# CC2650MCURadio.net
KiCad netlist of a schematic drawn in Altium Designer
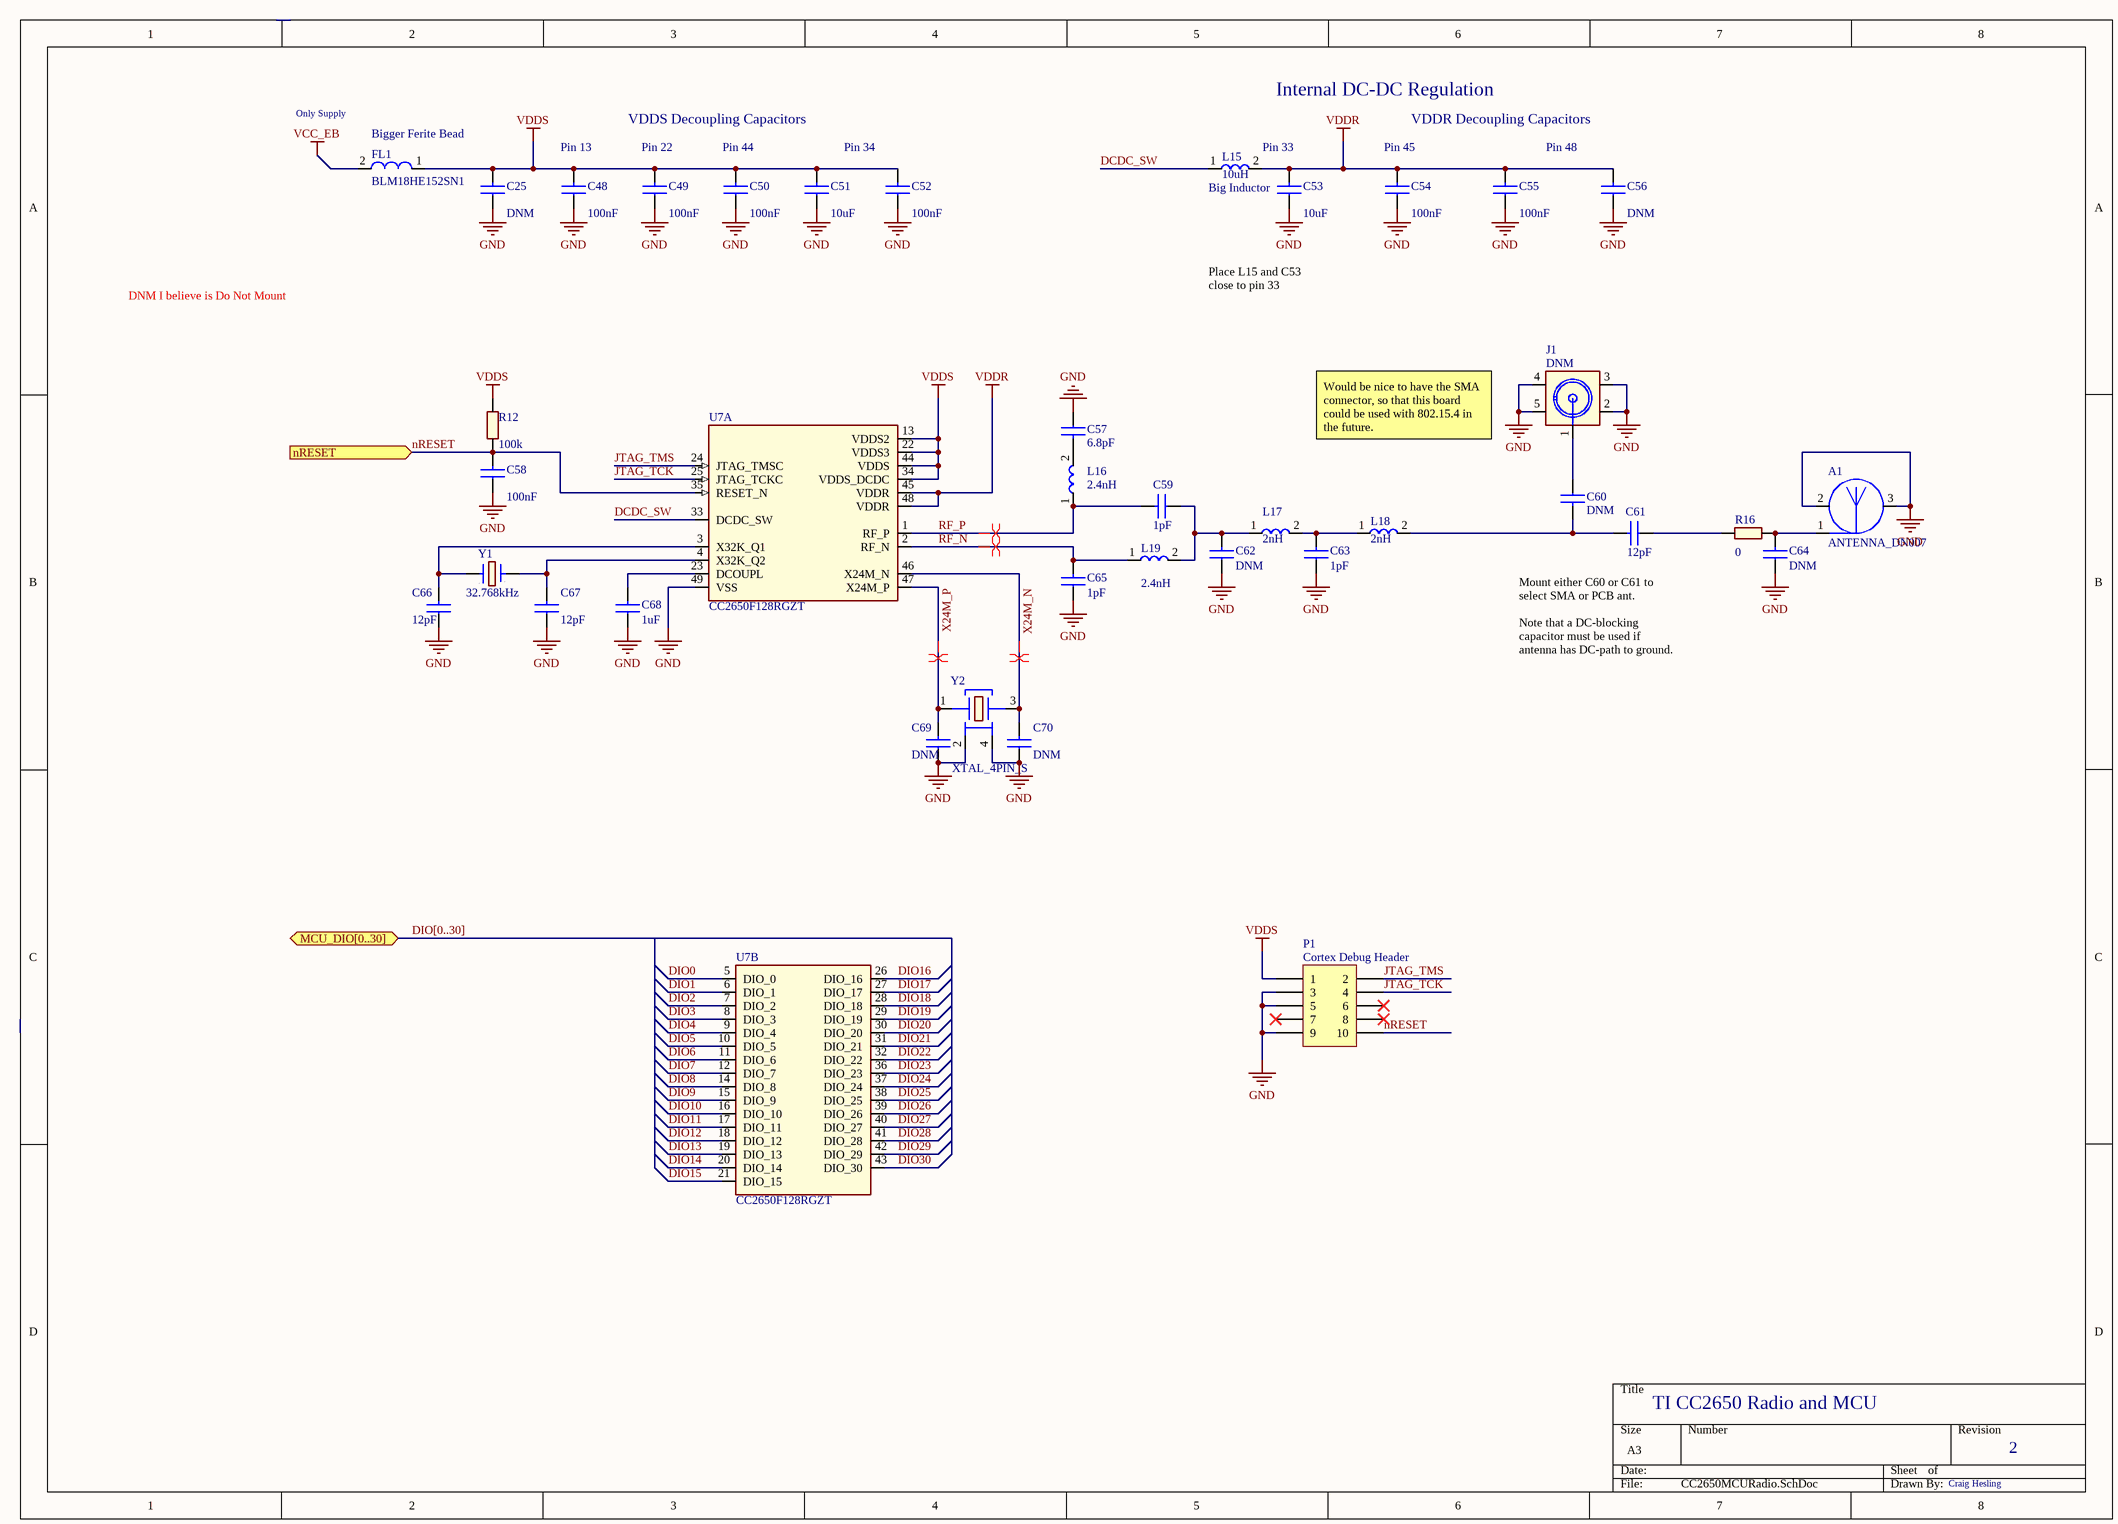
[diagram p0: CC2650MCURadio.SchDoc]

(export (version "E")
  (design (tool "Eeschema 10.0.6"))
  (components
    (comp (ref "A1")
      (value "ANTENNA_DN007")
      (footprint "ANTENNA_DN007AN_NO_MASK")
      (fields (field (name "DESIGNED BY") "Artur Bielinski"))
      (libsource (lib "CC26XX_7X7_DIFF_Library") (part "ANTENNA_DN007"))
    )
    (comp (ref "C25")
      (value "DNM")
      (footprint "CAPC0402(1005)60_N")
      (fields (field (name "VOLTAGE") "CMAX") (field (name "Comment") "CAPACITOR"))
      (libsource (lib "CC26XX_7X7_DIFF_Library") (part "CAPACITOR"))
    )
    (comp (ref "C48")
      (value "100nF")
      (footprint "CAPC0402(1005)60_N")
      (fields (field (name "VOLTAGE") "CMAX") (field (name "Comment") "CAPACITOR"))
      (libsource (lib "CC26XX_7X7_DIFF_Library") (part "CAPACITOR"))
    )
    (comp (ref "C49")
      (value "100nF")
      (footprint "CAPC0402(1005)60_N")
      (fields (field (name "VOLTAGE") "CMAX") (field (name "Comment") "CAPACITOR"))
      (libsource (lib "CC26XX_7X7_DIFF_Library") (part "CAPACITOR"))
    )
    (comp (ref "C50")
      (value "100nF")
      (footprint "CAPC0402(1005)60_N")
      (fields (field (name "VOLTAGE") "CMAX") (field (name "Comment") "CAPACITOR"))
      (libsource (lib "CC26XX_7X7_DIFF_Library") (part "CAPACITOR"))
    )
    (comp (ref "C51")
      (value "10uF")
      (footprint "CAPC0603(1608)100_N")
      (fields (field (name "VOLTAGE") "CMAX") (field (name "Comment") "CAPACITOR"))
      (libsource (lib "CC26XX_7X7_DIFF_Library") (part "CAPACITOR"))
    )
    (comp (ref "C52")
      (value "100nF")
      (footprint "CAPC0603(1608)100_N")
      (fields (field (name "VOLTAGE") "CMAX") (field (name "Comment") "CAPACITOR"))
      (libsource (lib "CC26XX_7X7_DIFF_Library") (part "CAPACITOR"))
    )
    (comp (ref "C53")
      (value "10uF")
      (footprint "CAPC0603(1608)100_N")
      (fields (field (name "VOLTAGE") "CMAX") (field (name "Comment") "CAPACITOR"))
      (libsource (lib "CC26XX_7X7_DIFF_Library") (part "CAPACITOR"))
    )
    (comp (ref "C54")
      (value "100nF")
      (footprint "CAPC0402(1005)60_N")
      (fields (field (name "VOLTAGE") "CMAX") (field (name "Comment") "CAPACITOR"))
      (libsource (lib "CC26XX_7X7_DIFF_Library") (part "CAPACITOR"))
    )
    (comp (ref "C55")
      (value "100nF")
      (footprint "CAPC0402(1005)60_N")
      (fields (field (name "VOLTAGE") "CMAX") (field (name "Comment") "CAPACITOR"))
      (libsource (lib "CC26XX_7X7_DIFF_Library") (part "CAPACITOR"))
    )
    (comp (ref "C56")
      (value "DNM")
      (footprint "CAPC0402(1005)60_N")
      (fields (field (name "VOLTAGE") "CMAX") (field (name "Comment") "CAPACITOR"))
      (libsource (lib "CC26XX_7X7_DIFF_Library") (part "CAPACITOR"))
    )
    (comp (ref "C57")
      (value "6.8pF")
      (footprint "CAPC0402(1005)60_N")
      (fields (field (name "VOLTAGE") "CMAX") (field (name "Comment") "CAPACITOR"))
      (libsource (lib "CC26XX_7X7_DIFF_Library") (part "CAPACITOR"))
    )
    (comp (ref "C58")
      (value "100nF")
      (footprint "CAPC0402(1005)60_N")
      (fields (field (name "VOLTAGE") "CMAX") (field (name "Comment") "CAPACITOR"))
      (libsource (lib "CC26XX_7X7_DIFF_Library") (part "CAPACITOR"))
    )
    (comp (ref "C59")
      (value "1pF")
      (footprint "CAPC0402(1005)60_N")
      (fields (field (name "VOLTAGE") "CMAX") (field (name "Comment") "CAPACITOR"))
      (libsource (lib "CC26XX_7X7_DIFF_Library") (part "CAPACITOR"))
    )
    (comp (ref "C60")
      (value "DNM")
      (footprint "CAPC0402(1005)60_N")
      (fields (field (name "VOLTAGE") "CMAX") (field (name "Comment") "CAPACITOR"))
      (libsource (lib "CC26XX_7X7_DIFF_Library") (part "CAPACITOR"))
    )
    (comp (ref "C61")
      (value "12pF")
      (footprint "CAPC0402(1005)60_N")
      (fields (field (name "VOLTAGE") "CMAX") (field (name "Comment") "CAPACITOR"))
      (libsource (lib "CC26XX_7X7_DIFF_Library") (part "CAPACITOR"))
    )
    (comp (ref "C62")
      (value "DNM")
      (footprint "CAPC0402(1005)60_N")
      (fields (field (name "VOLTAGE") "CMAX") (field (name "Comment") "CAPACITOR"))
      (libsource (lib "CC26XX_7X7_DIFF_Library") (part "CAPACITOR"))
    )
    (comp (ref "C63")
      (value "1pF")
      (footprint "CAPC0402(1005)60_N")
      (fields (field (name "VOLTAGE") "CMAX") (field (name "Comment") "CAPACITOR"))
      (libsource (lib "CC26XX_7X7_DIFF_Library") (part "CAPACITOR"))
    )
    (comp (ref "C64")
      (value "DNM")
      (footprint "CAPC0402(1005)60_N")
      (fields (field (name "VOLTAGE") "CMAX") (field (name "Comment") "CAPACITOR"))
      (libsource (lib "CC26XX_7X7_DIFF_Library") (part "CAPACITOR"))
    )
    (comp (ref "C65")
      (value "1pF")
      (footprint "CAPC0402(1005)60_N")
      (fields (field (name "VOLTAGE") "CMAX") (field (name "Comment") "CAPACITOR"))
      (libsource (lib "CC26XX_7X7_DIFF_Library") (part "CAPACITOR"))
    )
    (comp (ref "C66")
      (value "12pF")
      (footprint "CAPC0402(1005)60_N")
      (fields (field (name "VOLTAGE") "CMAX") (field (name "Comment") "CAPACITOR"))
      (libsource (lib "CC26XX_7X7_DIFF_Library") (part "CAPACITOR"))
    )
    (comp (ref "C67")
      (value "12pF")
      (footprint "CAPC0402(1005)60_N")
      (fields (field (name "VOLTAGE") "CMAX") (field (name "Comment") "CAPACITOR"))
      (libsource (lib "CC26XX_7X7_DIFF_Library") (part "CAPACITOR"))
    )
    (comp (ref "C68")
      (value "1uF")
      (footprint "CAPC0402(1005)60_N")
      (fields (field (name "VOLTAGE") "CMAX") (field (name "Comment") "CAPACITOR"))
      (libsource (lib "CC26XX_7X7_DIFF_Library") (part "CAPACITOR"))
    )
    (comp (ref "C69")
      (value "DNM")
      (footprint "CAPC0402(1005)60_N")
      (fields (field (name "VOLTAGE") "CMAX") (field (name "Comment") "CAPACITOR"))
      (libsource (lib "CC26XX_7X7_DIFF_Library") (part "CAPACITOR"))
    )
    (comp (ref "C70")
      (value "DNM")
      (footprint "CAPC0402(1005)60_N")
      (fields (field (name "VOLTAGE") "CMAX") (field (name "Comment") "CAPACITOR"))
      (libsource (lib "CC26XX_7X7_DIFF_Library") (part "CAPACITOR"))
    )
    (comp (ref "FL1")
      (value "BLM18HE152SN1")
      (footprint "FIL_BLM18HE152SN1DL")
      (libsource (lib "CC26XX_7X7_DIFF_Library") (part "FILTER_2PIN"))
    )
    (comp (ref "J1")
      (value "DNM")
      (footprint "HUSTSAN_SMA10V21TGGAN_POLYGONPOUR_CUTOUT")
      (libsource (lib "CC26XX_7X7_DIFF_Library") (part "CONN_COAX_1+4"))
    )
    (comp (ref "L15")
      (value "10uH")
      (footprint "CAPC0805(2012)75_N")
      (fields (field (name "Comment") "INDUCTOR"))
      (libsource (lib "CC26XX_7X7_DIFF_Library") (part "INDUCTOR"))
    )
    (comp (ref "L16")
      (value "2.4nH")
      (footprint "INDC1005X60L")
      (fields (field (name "Comment") "INDUCTOR"))
      (libsource (lib "CC26XX_7X7_DIFF_Library") (part "INDUCTOR"))
    )
    (comp (ref "L17")
      (value "2nH")
      (footprint "INDC1005X60L")
      (fields (field (name "Comment") "INDUCTOR"))
      (libsource (lib "CC26XX_7X7_DIFF_Library") (part "INDUCTOR"))
    )
    (comp (ref "L18")
      (value "2nH")
      (footprint "INDC1005X60L")
      (fields (field (name "Comment") "INDUCTOR"))
      (libsource (lib "CC26XX_7X7_DIFF_Library") (part "INDUCTOR"))
    )
    (comp (ref "L19")
      (value "2.4nH")
      (footprint "INDC1005X60L")
      (fields (field (name "Comment") "INDUCTOR"))
      (libsource (lib "CC26XX_7X7_DIFF_Library") (part "INDUCTOR"))
    )
    (comp (ref "P1")
      (value "Cortex Debug Header")
      (footprint "Header 1.27mm 2x5 SMD")
      (description "Header, 5-Pin, Dual row, Right Angle")
      (fields (field (name "PUBLISHER") "Altium Limited"))
      (libsource (lib "lib") (part "Header 5X2"))
    )
    (comp (ref "R12")
      (value "100k")
      (footprint "RESC1005X40L")
      (fields
        (field (name "VOLTAGE") "RVMAX")
        (field (name "POWER") "RMAX")
        (field (name "Comment") "RESISTOR")
      )
      (libsource (lib "CC26XX_7X7_DIFF_Library") (part "RESISTOR"))
    )
    (comp (ref "R16")
      (value "0")
      (footprint "RESC1005X40L")
      (fields
        (field (name "VOLTAGE") "RVMAX")
        (field (name "POWER") "RMAX")
        (field (name "Comment") "RESISTOR")
      )
      (libsource (lib "") (part "RESISTOR_1"))
    )
    (comp (ref "U7")
      (value "CC2650F128RGZT")
      (footprint "ExtraComponents:QFN50P700X700X100_HS-49N")
      (fields (field (name "DESIGNED_BY") "Artur Bielinski"))
      (libsource (lib "lib") (part "CC2650F128RGZT"))
    )
    (comp (ref "Y1")
      (value "CRYSTAL")
      (footprint "XTAL_FC-135N")
      (fields (field (name "FREQUENCY") "32.768kHz"))
      (libsource (lib "CC26XX_7X7_DIFF_Library") (part "CRYSTAL"))
    )
    (comp (ref "Y2")
      (value "XTAL_4PIN_S")
      (footprint "Crystal 4-SMD 5.0x3.2mm")
      (libsource (lib "CC26XX_7X7_DIFF_Library") (part "XTAL_4PIN_S"))
    )
  )
  (nets
    (net (code "1") (name "/DCDC_SW") (class "Default")
      (node (ref "L15") (pin "1") (pinfunction "1_1") (pintype "passive"))
      (node (ref "U7") (pin "33") (pinfunction "DCDC_SW_33") (pintype "power_in"))
    )
    (net (code "2") (name "/DIO0") (class "Default")
      (node (ref "U7") (pin "5") (pinfunction "DIO_0_5") (pintype "bidirectional"))
    )
    (net (code "3") (name "/DIO1") (class "Default")
      (node (ref "U7") (pin "6") (pinfunction "DIO_1_6") (pintype "bidirectional"))
    )
    (net (code "4") (name "/DIO2") (class "Default")
      (node (ref "U7") (pin "7") (pinfunction "DIO_2_7") (pintype "bidirectional"))
    )
    (net (code "5") (name "/DIO3") (class "Default")
      (node (ref "U7") (pin "8") (pinfunction "DIO_3_8") (pintype "bidirectional"))
    )
    (net (code "6") (name "/DIO4") (class "Default")
      (node (ref "U7") (pin "9") (pinfunction "DIO_4_9") (pintype "bidirectional"))
    )
    (net (code "7") (name "/DIO5") (class "Default")
      (node (ref "U7") (pin "10") (pinfunction "DIO_5_10") (pintype "bidirectional"))
    )
    (net (code "8") (name "/DIO6") (class "Default")
      (node (ref "U7") (pin "11") (pinfunction "DIO_6_11") (pintype "bidirectional"))
    )
    (net (code "9") (name "/DIO7") (class "Default")
      (node (ref "U7") (pin "12") (pinfunction "DIO_7_12") (pintype "bidirectional"))
    )
    (net (code "10") (name "/DIO8") (class "Default")
      (node (ref "U7") (pin "14") (pinfunction "DIO_8_14") (pintype "bidirectional"))
    )
    (net (code "11") (name "/DIO9") (class "Default")
      (node (ref "U7") (pin "15") (pinfunction "DIO_9_15") (pintype "bidirectional"))
    )
    (net (code "12") (name "/DIO10") (class "Default")
      (node (ref "U7") (pin "16") (pinfunction "DIO_10_16") (pintype "bidirectional"))
    )
    (net (code "13") (name "/DIO11") (class "Default")
      (node (ref "U7") (pin "17") (pinfunction "DIO_11_17") (pintype "bidirectional"))
    )
    (net (code "14") (name "/DIO12") (class "Default")
      (node (ref "U7") (pin "18") (pinfunction "DIO_12_18") (pintype "bidirectional"))
    )
    (net (code "15") (name "/DIO13") (class "Default")
      (node (ref "U7") (pin "19") (pinfunction "DIO_13_19") (pintype "bidirectional"))
    )
    (net (code "16") (name "/DIO14") (class "Default")
      (node (ref "U7") (pin "20") (pinfunction "DIO_14_20") (pintype "bidirectional"))
    )
    (net (code "17") (name "/DIO15") (class "Default")
      (node (ref "U7") (pin "21") (pinfunction "DIO_15_21") (pintype "bidirectional"))
    )
    (net (code "18") (name "/DIO16") (class "Default")
      (node (ref "U7") (pin "26") (pinfunction "DIO_16_26") (pintype "bidirectional"))
    )
    (net (code "19") (name "/DIO17") (class "Default")
      (node (ref "U7") (pin "27") (pinfunction "DIO_17_27") (pintype "bidirectional"))
    )
    (net (code "20") (name "/DIO18") (class "Default")
      (node (ref "U7") (pin "28") (pinfunction "DIO_18_28") (pintype "bidirectional"))
    )
    (net (code "21") (name "/DIO19") (class "Default")
      (node (ref "U7") (pin "29") (pinfunction "DIO_19_29") (pintype "bidirectional"))
    )
    (net (code "22") (name "/DIO20") (class "Default")
      (node (ref "U7") (pin "30") (pinfunction "DIO_20_30") (pintype "bidirectional"))
    )
    (net (code "23") (name "/DIO21") (class "Default")
      (node (ref "U7") (pin "31") (pinfunction "DIO_21_31") (pintype "bidirectional"))
    )
    (net (code "24") (name "/DIO22") (class "Default")
      (node (ref "U7") (pin "32") (pinfunction "DIO_22_32") (pintype "bidirectional"))
    )
    (net (code "25") (name "/DIO23") (class "Default")
      (node (ref "U7") (pin "36") (pinfunction "DIO_23_36") (pintype "bidirectional"))
    )
    (net (code "26") (name "/DIO24") (class "Default")
      (node (ref "U7") (pin "37") (pinfunction "DIO_24_37") (pintype "bidirectional"))
    )
    (net (code "27") (name "/DIO25") (class "Default")
      (node (ref "U7") (pin "38") (pinfunction "DIO_25_38") (pintype "bidirectional"))
    )
    (net (code "28") (name "/DIO26") (class "Default")
      (node (ref "U7") (pin "39") (pinfunction "DIO_26_39") (pintype "bidirectional"))
    )
    (net (code "29") (name "/DIO27") (class "Default")
      (node (ref "U7") (pin "40") (pinfunction "DIO_27_40") (pintype "bidirectional"))
    )
    (net (code "30") (name "/DIO28") (class "Default")
      (node (ref "U7") (pin "41") (pinfunction "DIO_28_41") (pintype "bidirectional"))
    )
    (net (code "31") (name "/DIO29") (class "Default")
      (node (ref "U7") (pin "42") (pinfunction "DIO_29_42") (pintype "bidirectional"))
    )
    (net (code "32") (name "/DIO30") (class "Default")
      (node (ref "U7") (pin "43") (pinfunction "DIO_30_43") (pintype "bidirectional"))
    )
    (net (code "34") (name "/JTAG_TCK") (class "Default")
      (node (ref "P1") (pin "4") (pinfunction "4_4") (pintype "passive"))
      (node (ref "U7") (pin "25") (pinfunction "JTAG_TCKC_25") (pintype "input"))
    )
    (net (code "35") (name "/JTAG_TMS") (class "Default")
      (node (ref "P1") (pin "2") (pinfunction "2_2") (pintype "passive"))
      (node (ref "U7") (pin "24") (pinfunction "JTAG_TMSC_24") (pintype "input"))
    )
    (net (code "36") (name "/RF_N") (class "Default")
      (node (ref "C65") (pin "2") (pinfunction "2_2") (pintype "passive"))
      (node (ref "L19") (pin "1") (pinfunction "1_1") (pintype "passive"))
      (node (ref "U7") (pin "2") (pinfunction "RF_N_2") (pintype "passive"))
    )
    (net (code "37") (name "/RF_P") (class "Default")
      (node (ref "C59") (pin "2") (pinfunction "2_2") (pintype "passive"))
      (node (ref "L16") (pin "1") (pinfunction "1_1") (pintype "passive"))
      (node (ref "U7") (pin "1") (pinfunction "RF_P_1") (pintype "passive"))
    )
    (net (code "38") (name "/X24M_N") (class "Default")
      (node (ref "C70") (pin "2") (pinfunction "2_2") (pintype "passive"))
      (node (ref "U7") (pin "46") (pinfunction "X24M_N_46") (pintype "passive"))
      (node (ref "Y2") (pin "3") (pinfunction "3_3") (pintype "passive"))
    )
    (net (code "39") (name "/X24M_P") (class "Default")
      (node (ref "C69") (pin "2") (pinfunction "2_2") (pintype "passive"))
      (node (ref "U7") (pin "47") (pinfunction "X24M_P_47") (pintype "passive"))
      (node (ref "Y2") (pin "1") (pinfunction "1_1") (pintype "passive"))
    )
    (net (code "40") (name "/nRESET") (class "Default")
      (node (ref "C58") (pin "2") (pinfunction "2_2") (pintype "passive"))
      (node (ref "P1") (pin "10") (pinfunction "10_10") (pintype "passive"))
      (node (ref "R12") (pin "1") (pinfunction "1_1") (pintype "passive"))
      (node (ref "U7") (pin "35") (pinfunction "RESET_N_35") (pintype "input"))
    )
    (net (code "41") (name "GND") (class "Default")
      (node (ref "A1") (pin "2") (pinfunction "GND_2_2") (pintype "passive"))
      (node (ref "A1") (pin "3") (pinfunction "GND_3_3") (pintype "passive"))
      (node (ref "C25") (pin "1") (pinfunction "1_1") (pintype "passive"))
      (node (ref "C48") (pin "1") (pinfunction "1_1") (pintype "passive"))
      (node (ref "C49") (pin "1") (pinfunction "1_1") (pintype "passive"))
      (node (ref "C50") (pin "1") (pinfunction "1_1") (pintype "passive"))
      (node (ref "C51") (pin "1") (pinfunction "1_1") (pintype "passive"))
      (node (ref "C52") (pin "1") (pinfunction "1_1") (pintype "passive"))
      (node (ref "C53") (pin "1") (pinfunction "1_1") (pintype "passive"))
      (node (ref "C54") (pin "1") (pinfunction "1_1") (pintype "passive"))
      (node (ref "C55") (pin "1") (pinfunction "1_1") (pintype "passive"))
      (node (ref "C56") (pin "1") (pinfunction "1_1") (pintype "passive"))
      (node (ref "C57") (pin "1") (pinfunction "1_1") (pintype "passive"))
      (node (ref "C58") (pin "1") (pinfunction "1_1") (pintype "passive"))
      (node (ref "C62") (pin "1") (pinfunction "1_1") (pintype "passive"))
      (node (ref "C63") (pin "1") (pinfunction "1_1") (pintype "passive"))
      (node (ref "C64") (pin "1") (pinfunction "1_1") (pintype "passive"))
      (node (ref "C65") (pin "1") (pinfunction "1_1") (pintype "passive"))
      (node (ref "C66") (pin "1") (pinfunction "1_1") (pintype "passive"))
      (node (ref "C67") (pin "1") (pinfunction "1_1") (pintype "passive"))
      (node (ref "C68") (pin "1") (pinfunction "1_1") (pintype "passive"))
      (node (ref "C69") (pin "1") (pinfunction "1_1") (pintype "passive"))
      (node (ref "C70") (pin "1") (pinfunction "1_1") (pintype "passive"))
      (node (ref "J1") (pin "2") (pinfunction "2_2") (pintype "power_in"))
      (node (ref "J1") (pin "3") (pinfunction "3_3") (pintype "power_in"))
      (node (ref "J1") (pin "4") (pinfunction "4_4") (pintype "power_in"))
      (node (ref "J1") (pin "5") (pinfunction "5_5") (pintype "power_in"))
      (node (ref "P1") (pin "3") (pinfunction "3_3") (pintype "passive"))
      (node (ref "P1") (pin "5") (pinfunction "5_5") (pintype "passive"))
      (node (ref "P1") (pin "9") (pinfunction "9_9") (pintype "passive"))
      (node (ref "U7") (pin "49") (pinfunction "VSS_49") (pintype "power_in"))
      (node (ref "Y2") (pin "2") (pinfunction "2_2") (pintype "power_in"))
      (node (ref "Y2") (pin "4") (pinfunction "4_4") (pintype "power_in"))
    )
    (net (code "42") (name "Net-(A1-FEED_1)") (class "Default")
      (node (ref "A1") (pin "1") (pinfunction "FEED_1_1") (pintype "passive"))
      (node (ref "C64") (pin "2") (pinfunction "2_2") (pintype "passive"))
      (node (ref "R16") (pin "1") (pinfunction "1_1") (pintype "passive"))
    )
    (net (code "43") (name "Net-(C57-Pad2)") (class "Default")
      (node (ref "C57") (pin "2") (pinfunction "2_2") (pintype "passive"))
      (node (ref "L16") (pin "2") (pinfunction "2_2") (pintype "passive"))
    )
    (net (code "44") (name "Net-(C59-Pad1)") (class "Default")
      (node (ref "C59") (pin "1") (pinfunction "1_1") (pintype "passive"))
      (node (ref "C62") (pin "2") (pinfunction "2_2") (pintype "passive"))
      (node (ref "L17") (pin "1") (pinfunction "1_1") (pintype "passive"))
      (node (ref "L19") (pin "2") (pinfunction "2_2") (pintype "passive"))
    )
    (net (code "45") (name "Net-(C60-Pad1)") (class "Default")
      (node (ref "C60") (pin "1") (pinfunction "1_1") (pintype "passive"))
      (node (ref "J1") (pin "1") (pinfunction "1_1") (pintype "passive"))
    )
    (net (code "46") (name "Net-(C60-Pad2)") (class "Default")
      (node (ref "C60") (pin "2") (pinfunction "2_2") (pintype "passive"))
      (node (ref "C61") (pin "2") (pinfunction "2_2") (pintype "passive"))
      (node (ref "L18") (pin "2") (pinfunction "2_2") (pintype "passive"))
    )
    (net (code "47") (name "Net-(C61-Pad1)") (class "Default")
      (node (ref "C61") (pin "1") (pinfunction "1_1") (pintype "passive"))
      (node (ref "R16") (pin "2") (pinfunction "2_2") (pintype "passive"))
    )
    (net (code "48") (name "Net-(C63-Pad2)") (class "Default")
      (node (ref "C63") (pin "2") (pinfunction "2_2") (pintype "passive"))
      (node (ref "L17") (pin "2") (pinfunction "2_2") (pintype "passive"))
      (node (ref "L18") (pin "1") (pinfunction "1_1") (pintype "passive"))
    )
    (net (code "49") (name "Net-(U7A-DCOUPL)") (class "Default")
      (node (ref "C68") (pin "2") (pinfunction "2_2") (pintype "passive"))
      (node (ref "U7") (pin "23") (pinfunction "DCOUPL_23") (pintype "passive"))
    )
    (net (code "50") (name "Net-(U7A-X32K_Q1)") (class "Default")
      (node (ref "C66") (pin "2") (pinfunction "2_2") (pintype "passive"))
      (node (ref "U7") (pin "3") (pinfunction "X32K_Q1_3") (pintype "passive"))
      (node (ref "Y1") (pin "1") (pinfunction "1_1") (pintype "passive"))
    )
    (net (code "51") (name "Net-(U7A-X32K_Q2)") (class "Default")
      (node (ref "C67") (pin "2") (pinfunction "2_2") (pintype "passive"))
      (node (ref "U7") (pin "4") (pinfunction "X32K_Q2_4") (pintype "passive"))
      (node (ref "Y1") (pin "2") (pinfunction "2_2") (pintype "passive"))
    )
    (net (code "52") (name "VCC_EB") (class "Default")
      (node (ref "FL1") (pin "2") (pinfunction "2_2") (pintype "passive"))
    )
    (net (code "53") (name "VDDR") (class "Default")
      (node (ref "C53") (pin "2") (pinfunction "2_2") (pintype "passive"))
      (node (ref "C54") (pin "2") (pinfunction "2_2") (pintype "passive"))
      (node (ref "C55") (pin "2") (pinfunction "2_2") (pintype "passive"))
      (node (ref "C56") (pin "2") (pinfunction "2_2") (pintype "passive"))
      (node (ref "L15") (pin "2") (pinfunction "2_2") (pintype "passive"))
      (node (ref "U7") (pin "45") (pinfunction "VDDR_45") (pintype "power_in"))
      (node (ref "U7") (pin "48") (pinfunction "VDDR_48") (pintype "power_in"))
    )
    (net (code "54") (name "VDDS") (class "Default")
      (node (ref "C25") (pin "2") (pinfunction "2_2") (pintype "passive"))
      (node (ref "C48") (pin "2") (pinfunction "2_2") (pintype "passive"))
      (node (ref "C49") (pin "2") (pinfunction "2_2") (pintype "passive"))
      (node (ref "C50") (pin "2") (pinfunction "2_2") (pintype "passive"))
      (node (ref "C51") (pin "2") (pinfunction "2_2") (pintype "passive"))
      (node (ref "C52") (pin "2") (pinfunction "2_2") (pintype "passive"))
      (node (ref "FL1") (pin "1") (pinfunction "1_1") (pintype "passive"))
      (node (ref "P1") (pin "1") (pinfunction "1_1") (pintype "passive"))
      (node (ref "R12") (pin "2") (pinfunction "2_2") (pintype "passive"))
      (node (ref "U7") (pin "13") (pinfunction "VDDS2_13") (pintype "power_in"))
      (node (ref "U7") (pin "22") (pinfunction "VDDS3_22") (pintype "power_in"))
      (node (ref "U7") (pin "34") (pinfunction "VDDS_DCDC_34") (pintype "power_in"))
      (node (ref "U7") (pin "44") (pinfunction "VDDS_44") (pintype "power_in"))
    )
    (net (code "55") (name "unconnected-(P1-Pad6)") (class "Default")
      (node (ref "P1") (pin "6") (pinfunction "6_6") (pintype "passive+no_connect"))
    )
    (net (code "56") (name "unconnected-(P1-Pad7)") (class "Default")
      (node (ref "P1") (pin "7") (pinfunction "7_7") (pintype "passive+no_connect"))
    )
    (net (code "57") (name "unconnected-(P1-Pad8)") (class "Default")
      (node (ref "P1") (pin "8") (pinfunction "8_8") (pintype "passive+no_connect"))
    )
  )
)
